# v6_mainboard_rpizerow.net
KiCad netlist of a schematic drawn in EAGLE
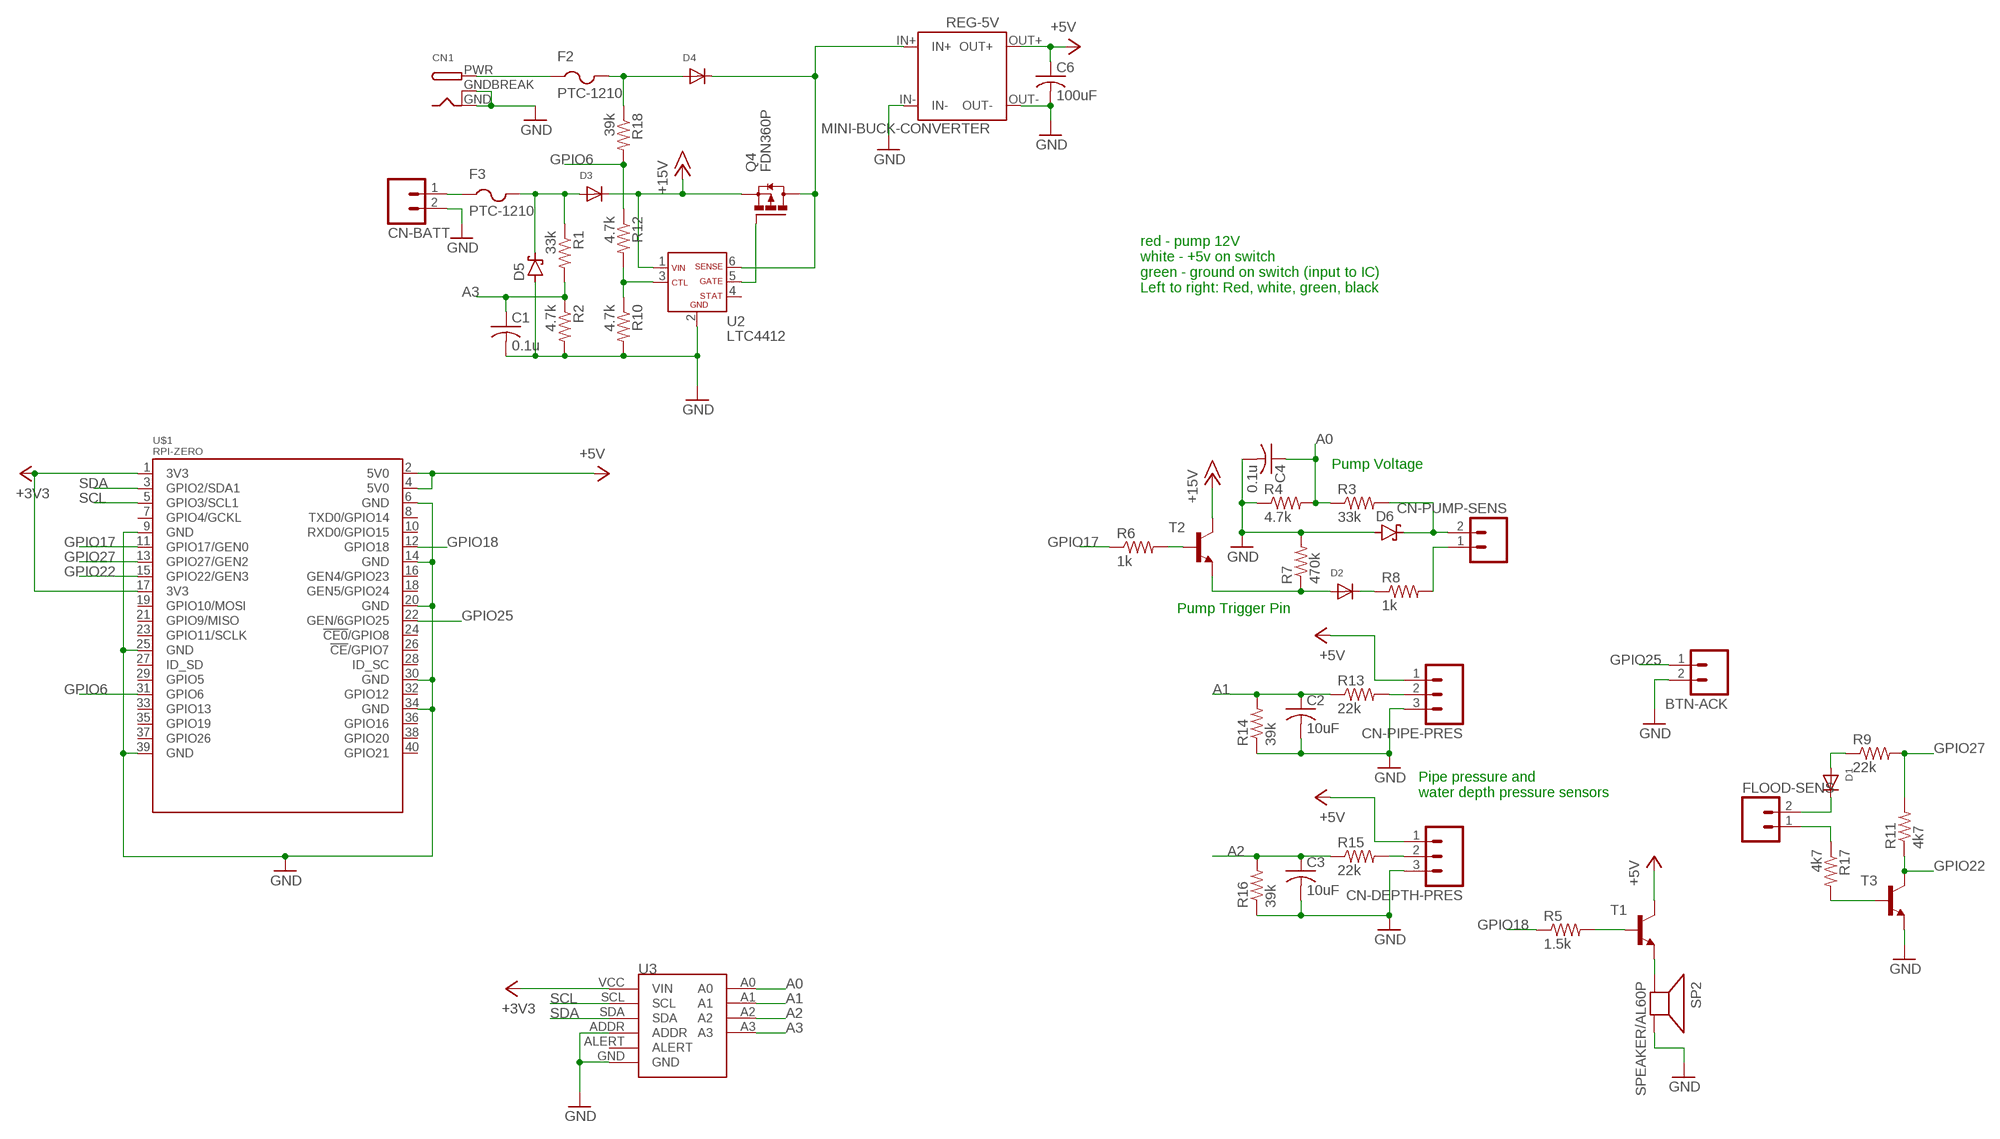
[diagram p0: schematic, sheet 1]

(export (version "E")
  (design (tool "Eeschema 10.0.6"))
  (components
    (comp (ref "BTN-ACK")
      (value "M02")
      (footprint "eagle-import:02P")
      (libsource (lib "eagle-import") (part "M02"))
    )
    (comp (ref "C1")
      (value "0.1u")
      (footprint "eagle-import:C0603K")
      (libsource (lib "eagle-import") (part "C-USC0603K"))
    )
    (comp (ref "C2")
      (value "10uF")
      (footprint "eagle-import:C0805K")
      (libsource (lib "eagle-import") (part "C-USC0805K"))
    )
    (comp (ref "C3")
      (value "10uF")
      (footprint "eagle-import:C0805K")
      (libsource (lib "eagle-import") (part "C-USC0805K"))
    )
    (comp (ref "C4")
      (value "0.1u")
      (footprint "eagle-import:C0603K")
      (libsource (lib "eagle-import") (part "C-USC0603K"))
    )
    (comp (ref "C6")
      (value "100uF")
      (footprint "eagle-import:C2220K")
      (libsource (lib "eagle-import") (part "C-USC2220K"))
    )
    (comp (ref "CN-BATT")
      (value "M02")
      (footprint "eagle-import:02P")
      (libsource (lib "eagle-import") (part "M02"))
    )
    (comp (ref "CN-DEPTH-PRES")
      (value "M03")
      (footprint "eagle-import:03P")
      (libsource (lib "eagle-import") (part "M03"))
    )
    (comp (ref "CN-PIPE-PRES")
      (value "M03")
      (footprint "eagle-import:03P")
      (libsource (lib "eagle-import") (part "M03"))
    )
    (comp (ref "CN-PUMP-SENS")
      (value "M02")
      (footprint "eagle-import:02P")
      (libsource (lib "eagle-import") (part "M02"))
    )
    (comp (ref "CN1")
      (value "DCBARRELPTH")
      (footprint "eagle-import:DCJACK_2MM_PTH")
      (libsource (lib "eagle-import") (part "DCBARRELPTH"))
    )
    (comp (ref "D1")
      (value "DIODESMA")
      (footprint "eagle-import:SMADIODE")
      (libsource (lib "eagle-import") (part "DIODESMA"))
    )
    (comp (ref "D2")
      (value "DIODESMA")
      (footprint "eagle-import:SMADIODE")
      (libsource (lib "eagle-import") (part "DIODESMA"))
    )
    (comp (ref "D3")
      (value "DIODESMA")
      (footprint "eagle-import:SMADIODE")
      (libsource (lib "eagle-import") (part "DIODESMA"))
    )
    (comp (ref "D4")
      (value "DIODESMA")
      (footprint "eagle-import:SMADIODE")
      (libsource (lib "eagle-import") (part "DIODESMA"))
    )
    (comp (ref "D5")
      (value "SCHOTTKY-DIODESMC")
      (footprint "eagle-import:SMC")
      (libsource (lib "eagle-import") (part "SCHOTTKY-DIODESMC"))
    )
    (comp (ref "D6")
      (value "SCHOTTKY-DIODESMC")
      (footprint "eagle-import:SMC")
      (libsource (lib "eagle-import") (part "SCHOTTKY-DIODESMC"))
    )
    (comp (ref "F2")
      (value "PTC-1210")
      (footprint "eagle-import:1210")
      (libsource (lib "eagle-import") (part "PTC-1210"))
    )
    (comp (ref "F3")
      (value "PTC-1210")
      (footprint "eagle-import:1210")
      (libsource (lib "eagle-import") (part "PTC-1210"))
    )
    (comp (ref "FLOOD-SENS")
      (value "M02")
      (footprint "eagle-import:02P")
      (libsource (lib "eagle-import") (part "M02"))
    )
    (comp (ref "Q4")
      (value "FDN360P")
      (footprint "eagle-import:SUPER-SOT3")
      (libsource (lib "eagle-import") (part "FDN360P"))
    )
    (comp (ref "R1")
      (value "33k")
      (footprint "eagle-import:R0603")
      (libsource (lib "eagle-import") (part "R-US_R0603"))
    )
    (comp (ref "R2")
      (value "4.7k")
      (footprint "eagle-import:R0603")
      (libsource (lib "eagle-import") (part "R-US_R0603"))
    )
    (comp (ref "R3")
      (value "33k")
      (footprint "eagle-import:R0603")
      (libsource (lib "eagle-import") (part "R-US_R0603"))
    )
    (comp (ref "R4")
      (value "4.7k")
      (footprint "eagle-import:R0603")
      (libsource (lib "eagle-import") (part "R-US_R0603"))
    )
    (comp (ref "R5")
      (value "1.5k")
      (footprint "eagle-import:R0603")
      (libsource (lib "eagle-import") (part "R-US_R0603"))
    )
    (comp (ref "R6")
      (value "1k")
      (footprint "eagle-import:R0603")
      (libsource (lib "eagle-import") (part "R-US_R0603"))
    )
    (comp (ref "R7")
      (value "470k")
      (footprint "eagle-import:R0603")
      (libsource (lib "eagle-import") (part "R-US_R0603"))
    )
    (comp (ref "R8")
      (value "1k")
      (footprint "eagle-import:R0603")
      (libsource (lib "eagle-import") (part "R-US_R0603"))
    )
    (comp (ref "R9")
      (value "22k")
      (footprint "eagle-import:R0603")
      (libsource (lib "eagle-import") (part "R-US_R0603"))
    )
    (comp (ref "R10")
      (value "4.7k")
      (footprint "eagle-import:R0603")
      (libsource (lib "eagle-import") (part "R-US_R0603"))
    )
    (comp (ref "R11")
      (value "4k7")
      (footprint "eagle-import:R0603")
      (libsource (lib "eagle-import") (part "R-US_R0603"))
    )
    (comp (ref "R12")
      (value "4.7k")
      (footprint "eagle-import:R0603")
      (libsource (lib "eagle-import") (part "R-US_R0603"))
    )
    (comp (ref "R13")
      (value "22k")
      (footprint "eagle-import:R0603")
      (libsource (lib "eagle-import") (part "R-US_R0603"))
    )
    (comp (ref "R14")
      (value "39k")
      (footprint "eagle-import:R0603")
      (libsource (lib "eagle-import") (part "R-US_R0603"))
    )
    (comp (ref "R15")
      (value "22k")
      (footprint "eagle-import:R0603")
      (libsource (lib "eagle-import") (part "R-US_R0603"))
    )
    (comp (ref "R16")
      (value "39k")
      (footprint "eagle-import:R0603")
      (libsource (lib "eagle-import") (part "R-US_R0603"))
    )
    (comp (ref "R17")
      (value "4k7")
      (footprint "eagle-import:R0603")
      (libsource (lib "eagle-import") (part "R-US_R0603"))
    )
    (comp (ref "R18")
      (value "39k")
      (footprint "eagle-import:R0603")
      (libsource (lib "eagle-import") (part "R-US_R0603"))
    )
    (comp (ref "REG-5V")
      (value "MINI-BUCK-CONVERTER")
      (footprint "eagle-import:MINI-BUCK-CONVERTER")
      (libsource (lib "eagle-import") (part "MINI-BUCK-CONVERTER"))
    )
    (comp (ref "SP2")
      (value "SPEAKER/AL60P")
      (footprint "eagle-import:AL60P")
      (libsource (lib "eagle-import") (part "SPEAKER/AL60P"))
    )
    (comp (ref "T1")
      (value "BC808-NPN-SOT23-BEC")
      (footprint "eagle-import:SOT23-BEC")
      (libsource (lib "eagle-import") (part "-NPN-SOT23-BECBC808"))
    )
    (comp (ref "T2")
      (value "BC808-NPN-SOT23-BEC")
      (footprint "eagle-import:SOT23-BEC")
      (libsource (lib "eagle-import") (part "-NPN-SOT23-BECBC808"))
    )
    (comp (ref "T3")
      (value "BC808-NPN-SOT23-BEC")
      (footprint "eagle-import:SOT23-BEC")
      (libsource (lib "eagle-import") (part "-NPN-SOT23-BECBC808"))
    )
    (comp (ref "U$1")
      (value "RPI-ZERO")
      (footprint "eagle-import:RASPBERRYPI_BASTELSTUBE_V13_RASPI_BOARD_B+_FULL")
      (libsource (lib "eagle-import") (part "RPI-ZERO"))
    )
    (comp (ref "U2")
      (value "LTC4412")
      (footprint "eagle-import:SOT23-6")
      (libsource (lib "eagle-import") (part "LTC4412"))
    )
    (comp (ref "U3")
      (value "GY-ADS1115THM")
      (footprint "eagle-import:GY-ADS1115-THM")
      (libsource (lib "eagle-import") (part "GY-ADS1115THM"))
    )
  )
  (nets
    (net (code "1") (name "+3V3") (class "Default")
      (node (ref "U$1") (pin "1") (pinfunction "3V3_1") (pintype "power_in"))
      (node (ref "U$1") (pin "17") (pinfunction "3V3_17") (pintype "power_in"))
      (node (ref "U3") (pin "VCC") (pinfunction "VIN_VCC") (pintype "bidirectional"))
    )
    (net (code "2") (name "+5V") (class "Default")
      (node (ref "C6") (pin "1") (pinfunction "1_1") (pintype "passive"))
      (node (ref "CN-DEPTH-PRES") (pin "1") (pinfunction "1_1") (pintype "passive"))
      (node (ref "CN-PIPE-PRES") (pin "1") (pinfunction "1_1") (pintype "passive"))
      (node (ref "REG-5V") (pin "OUT+") (pinfunction "OUT+_OUT+") (pintype "power_in"))
      (node (ref "T1") (pin "C") (pinfunction "C_C") (pintype "passive"))
      (node (ref "U$1") (pin "2") (pinfunction "5V0_2") (pintype "power_in"))
      (node (ref "U$1") (pin "4") (pinfunction "5V0_4") (pintype "power_in"))
    )
    (net (code "3") (name "+15V") (class "Default")
      (node (ref "D3") (pin "C") (pinfunction "C_C") (pintype "passive"))
      (node (ref "Q4") (pin "2") (pinfunction "S_2") (pintype "passive"))
      (node (ref "T2") (pin "C") (pinfunction "C_C") (pintype "passive"))
      (node (ref "U2") (pin "1") (pinfunction "VIN_1") (pintype "power_in"))
    )
    (net (code "4") (name "/A0") (class "Default")
      (node (ref "C4") (pin "1") (pinfunction "1_1") (pintype "passive"))
      (node (ref "R3") (pin "1") (pinfunction "1_1") (pintype "passive"))
      (node (ref "R4") (pin "2") (pinfunction "2_2") (pintype "passive"))
      (node (ref "U3") (pin "A0") (pinfunction "A0_A0") (pintype "bidirectional"))
    )
    (net (code "5") (name "/A1") (class "Default")
      (node (ref "C2") (pin "1") (pinfunction "1_1") (pintype "passive"))
      (node (ref "R13") (pin "1") (pinfunction "1_1") (pintype "passive"))
      (node (ref "R14") (pin "2") (pinfunction "2_2") (pintype "passive"))
      (node (ref "U3") (pin "A1") (pinfunction "A1_A1") (pintype "bidirectional"))
    )
    (net (code "6") (name "/A2") (class "Default")
      (node (ref "C3") (pin "1") (pinfunction "1_1") (pintype "passive"))
      (node (ref "R15") (pin "1") (pinfunction "1_1") (pintype "passive"))
      (node (ref "R16") (pin "2") (pinfunction "2_2") (pintype "passive"))
      (node (ref "U3") (pin "A2") (pinfunction "A2_A2") (pintype "bidirectional"))
    )
    (net (code "7") (name "/A3") (class "Default")
      (node (ref "C1") (pin "1") (pinfunction "1_1") (pintype "passive"))
      (node (ref "R1") (pin "2") (pinfunction "2_2") (pintype "passive"))
      (node (ref "R2") (pin "1") (pinfunction "1_1") (pintype "passive"))
      (node (ref "U3") (pin "A3") (pinfunction "A3_A3") (pintype "bidirectional"))
    )
    (net (code "8") (name "/GPIO6") (class "Default")
      (node (ref "R12") (pin "1") (pinfunction "1_1") (pintype "passive"))
      (node (ref "R18") (pin "2") (pinfunction "2_2") (pintype "passive"))
      (node (ref "U$1") (pin "31") (pinfunction "GPIO6_31") (pintype "bidirectional"))
    )
    (net (code "9") (name "/GPIO17") (class "Default")
      (node (ref "R6") (pin "1") (pinfunction "1_1") (pintype "passive"))
      (node (ref "U$1") (pin "11") (pinfunction "GPIO17/GEN0_11") (pintype "bidirectional"))
    )
    (net (code "10") (name "/GPIO18") (class "Default")
      (node (ref "R5") (pin "1") (pinfunction "1_1") (pintype "passive"))
      (node (ref "U$1") (pin "12") (pinfunction "GPIO18_12") (pintype "bidirectional"))
    )
    (net (code "11") (name "/GPIO22") (class "Default")
      (node (ref "R11") (pin "1") (pinfunction "1_1") (pintype "passive"))
      (node (ref "T3") (pin "C") (pinfunction "C_C") (pintype "passive"))
      (node (ref "U$1") (pin "15") (pinfunction "GPIO22/GEN3_15") (pintype "bidirectional"))
    )
    (net (code "12") (name "/GPIO25") (class "Default")
      (node (ref "BTN-ACK") (pin "1") (pinfunction "1_1") (pintype "passive"))
      (node (ref "U$1") (pin "22") (pinfunction "GEN/6GPIO25_22") (pintype "bidirectional"))
    )
    (net (code "13") (name "/GPIO27") (class "Default")
      (node (ref "R11") (pin "2") (pinfunction "2_2") (pintype "passive"))
      (node (ref "R9") (pin "2") (pinfunction "2_2") (pintype "passive"))
      (node (ref "U$1") (pin "13") (pinfunction "GPIO27/GEN2_13") (pintype "bidirectional"))
    )
    (net (code "14") (name "/SCL") (class "Default")
      (node (ref "U$1") (pin "5") (pinfunction "GPIO3/SCL1_5") (pintype "bidirectional"))
      (node (ref "U3") (pin "SCL") (pinfunction "SCL_SCL") (pintype "bidirectional"))
    )
    (net (code "15") (name "/SDA") (class "Default")
      (node (ref "U$1") (pin "3") (pinfunction "GPIO2/SDA1_3") (pintype "bidirectional"))
      (node (ref "U3") (pin "SDA") (pinfunction "SDA_SDA") (pintype "bidirectional"))
    )
    (net (code "16") (name "GND") (class "Default")
      (node (ref "BTN-ACK") (pin "2") (pinfunction "2_2") (pintype "passive"))
      (node (ref "C1") (pin "2") (pinfunction "2_2") (pintype "passive"))
      (node (ref "C2") (pin "2") (pinfunction "2_2") (pintype "passive"))
      (node (ref "C3") (pin "2") (pinfunction "2_2") (pintype "passive"))
      (node (ref "C4") (pin "2") (pinfunction "2_2") (pintype "passive"))
      (node (ref "C6") (pin "2") (pinfunction "2_2") (pintype "passive"))
      (node (ref "CN-BATT") (pin "2") (pinfunction "2_2") (pintype "passive"))
      (node (ref "CN-DEPTH-PRES") (pin "3") (pinfunction "3_3") (pintype "passive"))
      (node (ref "CN-PIPE-PRES") (pin "3") (pinfunction "3_3") (pintype "passive"))
      (node (ref "CN1") (pin "GND") (pinfunction "GND_GND") (pintype "power_in"))
      (node (ref "CN1") (pin "GNDBREAK") (pinfunction "GNDBREAK_GNDBREAK") (pintype "power_in"))
      (node (ref "D5") (pin "A") (pinfunction "A_A") (pintype "passive"))
      (node (ref "D6") (pin "A") (pinfunction "A_A") (pintype "passive"))
      (node (ref "R10") (pin "2") (pinfunction "2_2") (pintype "passive"))
      (node (ref "R14") (pin "1") (pinfunction "1_1") (pintype "passive"))
      (node (ref "R16") (pin "1") (pinfunction "1_1") (pintype "passive"))
      (node (ref "R2") (pin "2") (pinfunction "2_2") (pintype "passive"))
      (node (ref "R4") (pin "1") (pinfunction "1_1") (pintype "passive"))
      (node (ref "R7") (pin "2") (pinfunction "2_2") (pintype "passive"))
      (node (ref "REG-5V") (pin "IN-") (pinfunction "IN-_IN-") (pintype "power_in"))
      (node (ref "REG-5V") (pin "OUT-") (pinfunction "OUT-_OUT-") (pintype "power_in"))
      (node (ref "SP2") (pin "2") (pinfunction "-_2") (pintype "passive"))
      (node (ref "T3") (pin "E") (pinfunction "E_E") (pintype "passive"))
      (node (ref "U$1") (pin "14") (pinfunction "GND_14") (pintype "power_in"))
      (node (ref "U$1") (pin "20") (pinfunction "GND_20") (pintype "power_in"))
      (node (ref "U$1") (pin "25") (pinfunction "GND_25") (pintype "power_in"))
      (node (ref "U$1") (pin "30") (pinfunction "GND_30") (pintype "power_in"))
      (node (ref "U$1") (pin "34") (pinfunction "GND_34") (pintype "power_in"))
      (node (ref "U$1") (pin "39") (pinfunction "GND_39") (pintype "power_in"))
      (node (ref "U$1") (pin "6") (pinfunction "GND_6") (pintype "power_in"))
      (node (ref "U$1") (pin "9") (pinfunction "GND_9") (pintype "power_in"))
      (node (ref "U2") (pin "2") (pinfunction "GND_2") (pintype "power_in"))
      (node (ref "U3") (pin "ADDR") (pinfunction "ADDR_ADDR") (pintype "bidirectional"))
      (node (ref "U3") (pin "GND") (pinfunction "GND_GND") (pintype "bidirectional"))
    )
    (net (code "17") (name "Net-(CN-BATT-Pad1)") (class "Default")
      (node (ref "CN-BATT") (pin "1") (pinfunction "1_1") (pintype "passive"))
      (node (ref "F3") (pin "1") (pinfunction "1_1") (pintype "passive"))
    )
    (net (code "18") (name "Net-(CN-DEPTH-PRES-Pad2)") (class "Default")
      (node (ref "CN-DEPTH-PRES") (pin "2") (pinfunction "2_2") (pintype "passive"))
      (node (ref "R15") (pin "2") (pinfunction "2_2") (pintype "passive"))
    )
    (net (code "19") (name "Net-(CN-PIPE-PRES-Pad2)") (class "Default")
      (node (ref "CN-PIPE-PRES") (pin "2") (pinfunction "2_2") (pintype "passive"))
      (node (ref "R13") (pin "2") (pinfunction "2_2") (pintype "passive"))
    )
    (net (code "20") (name "Net-(CN-PUMP-SENS-Pad1)") (class "Default")
      (node (ref "CN-PUMP-SENS") (pin "1") (pinfunction "1_1") (pintype "passive"))
      (node (ref "R8") (pin "2") (pinfunction "2_2") (pintype "passive"))
    )
    (net (code "21") (name "Net-(CN-PUMP-SENS-Pad2)") (class "Default")
      (node (ref "CN-PUMP-SENS") (pin "2") (pinfunction "2_2") (pintype "passive"))
      (node (ref "D6") (pin "C") (pinfunction "C_C") (pintype "passive"))
      (node (ref "R3") (pin "2") (pinfunction "2_2") (pintype "passive"))
    )
    (net (code "22") (name "Net-(CN1-PadPWR)") (class "Default")
      (node (ref "CN1") (pin "PWR") (pinfunction "PWR_PWR") (pintype "power_in"))
      (node (ref "F2") (pin "1") (pinfunction "1_1") (pintype "passive"))
    )
    (net (code "23") (name "Net-(D1-PadA)") (class "Default")
      (node (ref "D1") (pin "A") (pinfunction "A_A") (pintype "passive"))
      (node (ref "R9") (pin "1") (pinfunction "1_1") (pintype "passive"))
    )
    (net (code "24") (name "Net-(D1-PadC)") (class "Default")
      (node (ref "D1") (pin "C") (pinfunction "C_C") (pintype "passive"))
      (node (ref "FLOOD-SENS") (pin "2") (pinfunction "2_2") (pintype "passive"))
    )
    (net (code "25") (name "Net-(D2-PadA)") (class "Default")
      (node (ref "D2") (pin "A") (pinfunction "A_A") (pintype "passive"))
      (node (ref "R7") (pin "1") (pinfunction "1_1") (pintype "passive"))
      (node (ref "T2") (pin "E") (pinfunction "E_E") (pintype "passive"))
    )
    (net (code "26") (name "Net-(D2-PadC)") (class "Default")
      (node (ref "D2") (pin "C") (pinfunction "C_C") (pintype "passive"))
      (node (ref "R8") (pin "1") (pinfunction "1_1") (pintype "passive"))
    )
    (net (code "27") (name "Net-(D3-PadA)") (class "Default")
      (node (ref "D3") (pin "A") (pinfunction "A_A") (pintype "passive"))
      (node (ref "D5") (pin "C") (pinfunction "C_C") (pintype "passive"))
      (node (ref "F3") (pin "2") (pinfunction "2_2") (pintype "passive"))
      (node (ref "R1") (pin "1") (pinfunction "1_1") (pintype "passive"))
    )
    (net (code "28") (name "Net-(D4-PadA)") (class "Default")
      (node (ref "D4") (pin "A") (pinfunction "A_A") (pintype "passive"))
      (node (ref "F2") (pin "2") (pinfunction "2_2") (pintype "passive"))
      (node (ref "R18") (pin "1") (pinfunction "1_1") (pintype "passive"))
    )
    (net (code "29") (name "Net-(FLOOD-SENS-Pad1)") (class "Default")
      (node (ref "FLOOD-SENS") (pin "1") (pinfunction "1_1") (pintype "passive"))
      (node (ref "R17") (pin "1") (pinfunction "1_1") (pintype "passive"))
    )
    (net (code "30") (name "Net-(Q4-D)") (class "Default")
      (node (ref "D4") (pin "C") (pinfunction "C_C") (pintype "passive"))
      (node (ref "Q4") (pin "3") (pinfunction "D_3") (pintype "passive"))
      (node (ref "REG-5V") (pin "IN+") (pinfunction "IN+_IN+") (pintype "power_in"))
      (node (ref "U2") (pin "6") (pinfunction "SENSE_6") (pintype "input"))
    )
    (net (code "31") (name "Net-(Q4-G)") (class "Default")
      (node (ref "Q4") (pin "1") (pinfunction "G_1") (pintype "passive"))
      (node (ref "U2") (pin "5") (pinfunction "GATE_5") (pintype "output"))
    )
    (net (code "32") (name "Net-(R5-Pad2)") (class "Default")
      (node (ref "R5") (pin "2") (pinfunction "2_2") (pintype "passive"))
      (node (ref "T1") (pin "B") (pinfunction "B_B") (pintype "passive"))
    )
    (net (code "33") (name "Net-(R6-Pad2)") (class "Default")
      (node (ref "R6") (pin "2") (pinfunction "2_2") (pintype "passive"))
      (node (ref "T2") (pin "B") (pinfunction "B_B") (pintype "passive"))
    )
    (net (code "34") (name "Net-(R17-Pad2)") (class "Default")
      (node (ref "R17") (pin "2") (pinfunction "2_2") (pintype "passive"))
      (node (ref "T3") (pin "B") (pinfunction "B_B") (pintype "passive"))
    )
    (net (code "35") (name "Net-(SP2-+)") (class "Default")
      (node (ref "SP2") (pin "1") (pinfunction "+_1") (pintype "passive"))
      (node (ref "T1") (pin "E") (pinfunction "E_E") (pintype "passive"))
    )
    (net (code "36") (name "Net-(U2-CTL)") (class "Default")
      (node (ref "R10") (pin "1") (pinfunction "1_1") (pintype "passive"))
      (node (ref "R12") (pin "2") (pinfunction "2_2") (pintype "passive"))
      (node (ref "U2") (pin "3") (pinfunction "CTL_3") (pintype "input"))
    )
    (net (code "37") (name "unconnected-(U$1-GEN4{slash}GPIO23-Pad16)") (class "Default")
      (node (ref "U$1") (pin "16") (pinfunction "GEN4/GPIO23_16") (pintype "bidirectional"))
    )
    (net (code "38") (name "unconnected-(U$1-GEN5{slash}GPIO24-Pad18)") (class "Default")
      (node (ref "U$1") (pin "18") (pinfunction "GEN5/GPIO24_18") (pintype "bidirectional"))
    )
    (net (code "39") (name "unconnected-(U$1-GPIO4{slash}GCKL-Pad7)") (class "Default")
      (node (ref "U$1") (pin "7") (pinfunction "GPIO4/GCKL_7") (pintype "bidirectional"))
    )
    (net (code "40") (name "unconnected-(U$1-GPIO5-Pad29)") (class "Default")
      (node (ref "U$1") (pin "29") (pinfunction "GPIO5_29") (pintype "bidirectional"))
    )
    (net (code "41") (name "unconnected-(U$1-GPIO9{slash}MISO-Pad21)") (class "Default")
      (node (ref "U$1") (pin "21") (pinfunction "GPIO9/MISO_21") (pintype "bidirectional"))
    )
    (net (code "42") (name "unconnected-(U$1-GPIO10{slash}MOSI-Pad19)") (class "Default")
      (node (ref "U$1") (pin "19") (pinfunction "GPIO10/MOSI_19") (pintype "bidirectional"))
    )
    (net (code "43") (name "unconnected-(U$1-GPIO11{slash}SCLK-Pad23)") (class "Default")
      (node (ref "U$1") (pin "23") (pinfunction "GPIO11/SCLK_23") (pintype "bidirectional"))
    )
    (net (code "44") (name "unconnected-(U$1-GPIO12-Pad32)") (class "Default")
      (node (ref "U$1") (pin "32") (pinfunction "GPIO12_32") (pintype "bidirectional"))
    )
    (net (code "45") (name "unconnected-(U$1-GPIO13-Pad33)") (class "Default")
      (node (ref "U$1") (pin "33") (pinfunction "GPIO13_33") (pintype "bidirectional"))
    )
    (net (code "46") (name "unconnected-(U$1-GPIO16-Pad36)") (class "Default")
      (node (ref "U$1") (pin "36") (pinfunction "GPIO16_36") (pintype "bidirectional"))
    )
    (net (code "47") (name "unconnected-(U$1-GPIO19-Pad35)") (class "Default")
      (node (ref "U$1") (pin "35") (pinfunction "GPIO19_35") (pintype "bidirectional"))
    )
    (net (code "48") (name "unconnected-(U$1-GPIO20-Pad38)") (class "Default")
      (node (ref "U$1") (pin "38") (pinfunction "GPIO20_38") (pintype "bidirectional"))
    )
    (net (code "49") (name "unconnected-(U$1-GPIO21-Pad40)") (class "Default")
      (node (ref "U$1") (pin "40") (pinfunction "GPIO21_40") (pintype "bidirectional"))
    )
    (net (code "50") (name "unconnected-(U$1-GPIO26-Pad37)") (class "Default")
      (node (ref "U$1") (pin "37") (pinfunction "GPIO26_37") (pintype "bidirectional"))
    )
    (net (code "51") (name "unconnected-(U$1-ID_SC-Pad28)") (class "Default")
      (node (ref "U$1") (pin "28") (pinfunction "ID_SC_28") (pintype "bidirectional"))
    )
    (net (code "52") (name "unconnected-(U$1-ID_SD-Pad27)") (class "Default")
      (node (ref "U$1") (pin "27") (pinfunction "ID_SD_27") (pintype "bidirectional"))
    )
    (net (code "53") (name "unconnected-(U$1-RXD0{slash}GPIO15-Pad10)") (class "Default")
      (node (ref "U$1") (pin "10") (pinfunction "RXD0/GPIO15_10") (pintype "bidirectional"))
    )
    (net (code "54") (name "unconnected-(U$1-TXD0{slash}GPIO14-Pad8)") (class "Default")
      (node (ref "U$1") (pin "8") (pinfunction "TXD0/GPIO14_8") (pintype "bidirectional"))
    )
    (net (code "55") (name "unconnected-(U$1-~{CE0}{slash}GPIO8-Pad24)") (class "Default")
      (node (ref "U$1") (pin "24") (pinfunction "~{CE0}/GPIO8_24") (pintype "bidirectional"))
    )
    (net (code "56") (name "unconnected-(U$1-~{CE}{slash}GPIO7-Pad26)") (class "Default")
      (node (ref "U$1") (pin "26") (pinfunction "~{CE}/GPIO7_26") (pintype "bidirectional"))
    )
    (net (code "57") (name "unconnected-(U2-STAT-Pad4)") (class "Default")
      (node (ref "U2") (pin "4") (pinfunction "STAT_4") (pintype "open_collector"))
    )
    (net (code "58") (name "unconnected-(U3-PadALERT)") (class "Default")
      (node (ref "U3") (pin "ALERT") (pinfunction "ALERT_ALERT") (pintype "bidirectional"))
    )
  )
)
